# ClosedLoop_Drive_UserInterface.net
KiCad netlist of a schematic drawn in Altium Designer
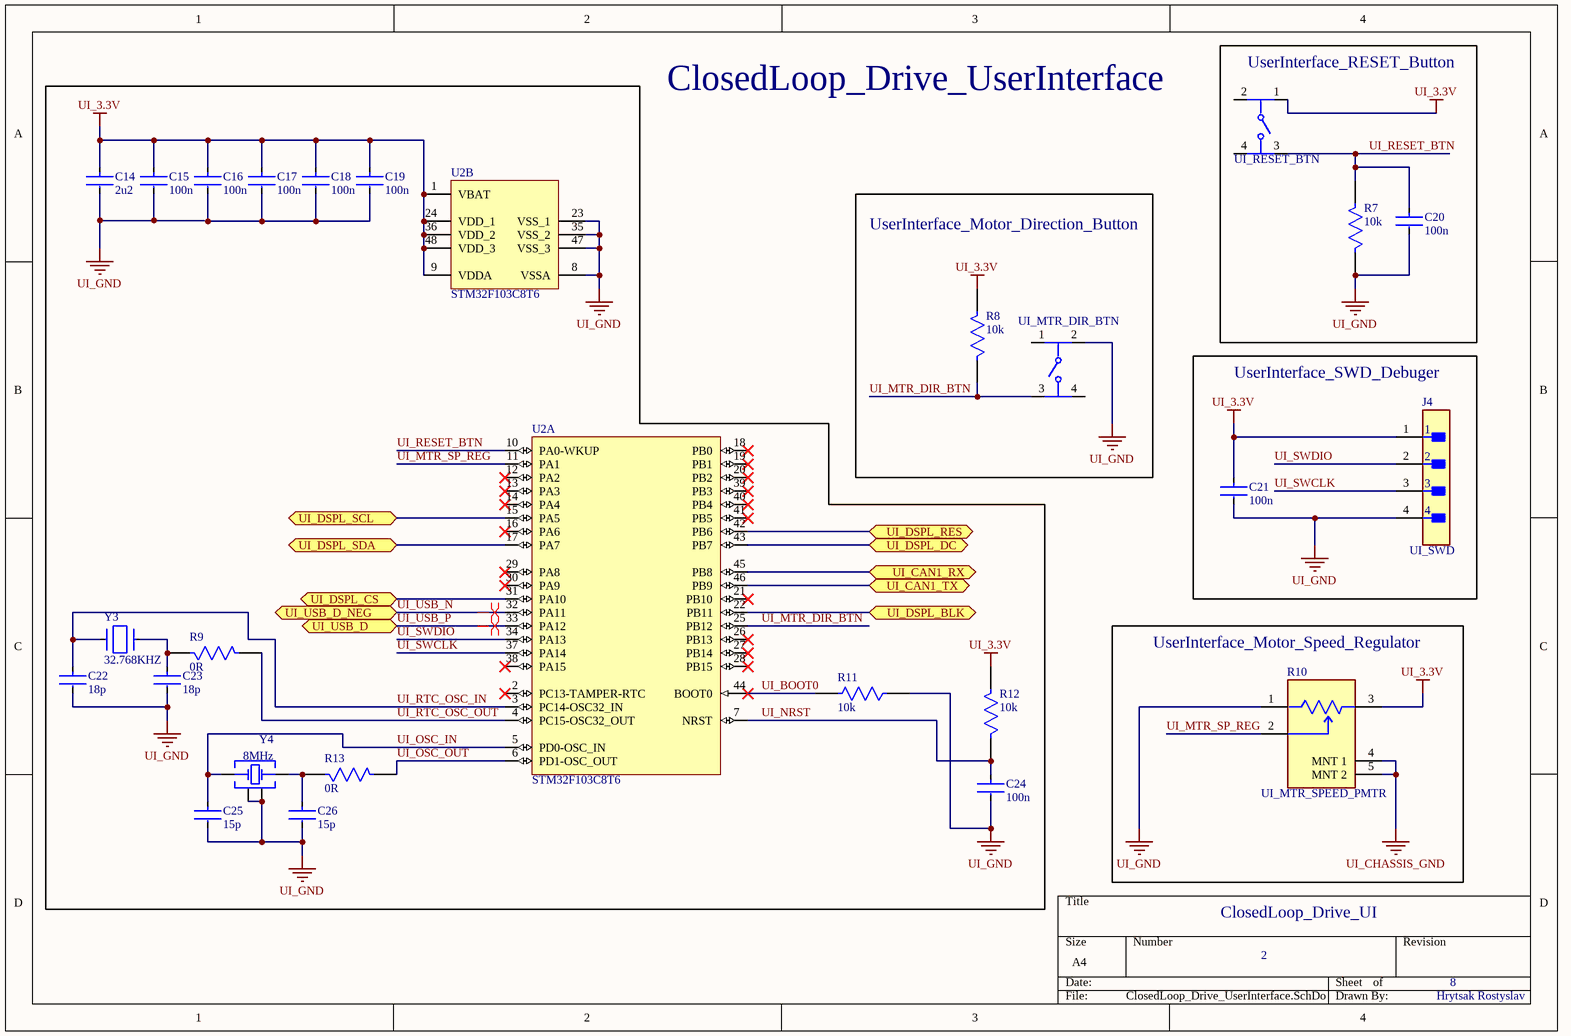
[diagram p0: ClosedLoop_Drive_UserInterface.SchDoc]

(export (version "E")
  (design (tool "Eeschema 10.0.6"))
  (components
    (comp (ref "C14")
      (value "2u2")
      (footprint "FP-0805-L_2_01_0_2-W_1_25-MFG")
      (description "0805")
      (fields (field (name "TOLERANCE") "10%"))
      (libsource (lib "Altium Content Vault") (part "b4654b650e69147ec39a6b967a45e02"))
    )
    (comp (ref "C15")
      (value "100n")
      (footprint "FP-0805-L_2_01_0_2-W_1_25-MFG")
      (description "0805")
      (fields (field (name "TOLERANCE") "10%"))
      (libsource (lib "Altium Content Vault") (part "b4654b650e69147ec39a6b967a45e02"))
    )
    (comp (ref "C16")
      (value "100n")
      (footprint "FP-0805-L_2_01_0_2-W_1_25-MFG")
      (description "0805")
      (fields (field (name "TOLERANCE") "10%"))
      (libsource (lib "Altium Content Vault") (part "b4654b650e69147ec39a6b967a45e02"))
    )
    (comp (ref "C17")
      (value "100n")
      (footprint "FP-0805-L_2_01_0_2-W_1_25-MFG")
      (description "0805")
      (fields (field (name "TOLERANCE") "10%"))
      (libsource (lib "Altium Content Vault") (part "b4654b650e69147ec39a6b967a45e02"))
    )
    (comp (ref "C18")
      (value "100n")
      (footprint "FP-0805-L_2_01_0_2-W_1_25-MFG")
      (description "0805")
      (fields (field (name "TOLERANCE") "10%"))
      (libsource (lib "Altium Content Vault") (part "b4654b650e69147ec39a6b967a45e02"))
    )
    (comp (ref "C19")
      (value "100n")
      (footprint "FP-0805-L_2_01_0_2-W_1_25-MFG")
      (description "0805")
      (fields (field (name "TOLERANCE") "10%"))
      (libsource (lib "Altium Content Vault") (part "b4654b650e69147ec39a6b967a45e02"))
    )
    (comp (ref "C20")
      (value "100n")
      (footprint "FP-0805-L_2_01_0_2-W_1_25-MFG")
      (description "0805")
      (fields (field (name "TOLERANCE") "10%"))
      (libsource (lib "Altium Content Vault") (part "b4654b650e69147ec39a6b967a45e02"))
    )
    (comp (ref "C21")
      (value "100n")
      (footprint "FP-0805-L_2_01_0_2-W_1_25-MFG")
      (description "0805")
      (fields (field (name "TOLERANCE") "10%"))
      (libsource (lib "Altium Content Vault") (part "b4654b650e69147ec39a6b967a45e02"))
    )
    (comp (ref "C22")
      (value "18p")
      (footprint "FP-0805-L_2_01_0_2-W_1_25-MFG")
      (description "0805")
      (fields (field (name "TOLERANCE") "10%"))
      (libsource (lib "Altium Content Vault") (part "b4654b650e69147ec39a6b967a45e02"))
    )
    (comp (ref "C23")
      (value "18p")
      (footprint "FP-0805-L_2_01_0_2-W_1_25-MFG")
      (description "0805")
      (fields (field (name "TOLERANCE") "10%"))
      (libsource (lib "Altium Content Vault") (part "b4654b650e69147ec39a6b967a45e02"))
    )
    (comp (ref "C24")
      (value "100n")
      (footprint "FP-0805-L_2_01_0_2-W_1_25-MFG")
      (description "0805")
      (fields (field (name "TOLERANCE") "10%"))
      (libsource (lib "Altium Content Vault") (part "b4654b650e69147ec39a6b967a45e02"))
    )
    (comp (ref "C25")
      (value "15p")
      (footprint "FP-0805-L_2_01_0_2-W_1_25-MFG")
      (description "0805")
      (fields (field (name "TOLERANCE") "10%"))
      (libsource (lib "Altium Content Vault") (part "b4654b650e69147ec39a6b967a45e02"))
    )
    (comp (ref "C26")
      (value "15p")
      (footprint "FP-0805-L_2_01_0_2-W_1_25-MFG")
      (description "0805")
      (fields (field (name "TOLERANCE") "10%"))
      (libsource (lib "Altium Content Vault") (part "b4654b650e69147ec39a6b967a45e02"))
    )
    (comp (ref "J4")
      (value "UI_SWD")
      (footprint "FP-TSW-104-22-G-S-MFG")
      (description "CONN HEADER VERT 4POS 2.54MM")
      (libsource (lib "Altium Content Vault") (part "299a8cea1bdcbc3624fe62c390fa72c"))
    )
    (comp (ref "R7")
      (value "10k")
      (footprint "FP-MCU0805-IPC_A")
      (description "0805")
      (fields (field (name "TOLERANCE") "0.5%"))
      (libsource (lib "Altium Content Vault") (part "1029c3af85768c4190bb7ad29bc67b5"))
    )
    (comp (ref "R8")
      (value "10k")
      (footprint "FP-MCU0805-IPC_A")
      (description "0805")
      (fields (field (name "TOLERANCE") "0.5%"))
      (libsource (lib "Altium Content Vault") (part "1029c3af85768c4190bb7ad29bc67b5"))
    )
    (comp (ref "R9")
      (value "0R")
      (footprint "FP-MCU0805-IPC_A")
      (description "0805")
      (fields (field (name "TOLERANCE") "0.5%"))
      (libsource (lib "Altium Content Vault") (part "1029c3af85768c4190bb7ad29bc67b5"))
    )
    (comp (ref "R10")
      (value "UI_MTR_SPEED_PMTR")
      (footprint "FP-PTV09A-4-MFG")
      (description "POT 10K OHM 1/20W CARBON LINEAR")
      (fields (field (name "TOLERANCE") "20%"))
      (libsource (lib "Altium Content Vault") (part "705d11b747745a787204d796a5f3d12"))
    )
    (comp (ref "R11")
      (value "10k")
      (footprint "FP-MCU0805-IPC_A")
      (description "0805")
      (fields (field (name "TOLERANCE") "0.5%"))
      (libsource (lib "Altium Content Vault") (part "1029c3af85768c4190bb7ad29bc67b5"))
    )
    (comp (ref "R12")
      (value "10k")
      (footprint "FP-MCU0805-IPC_A")
      (description "0805")
      (fields (field (name "TOLERANCE") "0.5%"))
      (libsource (lib "Altium Content Vault") (part "1029c3af85768c4190bb7ad29bc67b5"))
    )
    (comp (ref "R13")
      (value "0R")
      (footprint "FP-MCU0805-IPC_A")
      (description "0805")
      (fields (field (name "TOLERANCE") "0.5%"))
      (libsource (lib "Altium Content Vault") (part "1029c3af85768c4190bb7ad29bc67b5"))
    )
    (comp (ref "U2")
      (value "STM32F103C8T6")
      (footprint "STM-LQFP48_L")
      (libsource (lib "Altium Content Vault") (part "MC-ARM-STM32F103X8_B-SQ48"))
    )
    (comp (ref "UI_MTR_DIR_BTN")
      (value "~")
      (footprint "FP-1-1977223-9-MFG")
      (description "SWITCH TACTILE SPST-NO 0.05A 24V")
      (libsource (lib "Altium Content Vault") (part "b8895f3f4cefb76e1819d2863dba89b"))
    )
    (comp (ref "UI_RESET_BTN")
      (value "~")
      (footprint "FP-1-1977223-9-MFG")
      (description "SWITCH TACTILE SPST-NO 0.05A 24V")
      (libsource (lib "Altium Content Vault") (part "b8895f3f4cefb76e1819d2863dba89b"))
    )
    (comp (ref "Y3")
      (value "32.768KHZ")
      (footprint "FP-NX2012SA-MFG")
      (description "CRYSTAL 32.7680KHZ 12.5PF SMD")
      (libsource (lib "Altium Content Vault") (part "c23a69dc6c9e2f18f2079038eb95dd1"))
    )
    (comp (ref "Y4")
      (value "8MHz")
      (footprint "WE-XTAL_12SMX")
      (description "WE-XTAL Quartz Crystal")
      (libsource (lib "Altium Content Vault") (part "WE-XTAL_12SMX"))
    )
  )
  (nets
    (net (code "1") (name "/UI_BOOT0") (class "Default")
      (node (ref "R11") (pin "2") (pinfunction "2_2") (pintype "passive"))
      (node (ref "U2") (pin "44") (pinfunction "BOOT0_44") (pintype "input"))
    )
    (net (code "2") (name "/UI_CAN1_RX") (class "Default")
      (node (ref "U2") (pin "45") (pinfunction "PB8_45") (pintype "bidirectional"))
    )
    (net (code "3") (name "/UI_CAN1_TX") (class "Default")
      (node (ref "U2") (pin "46") (pinfunction "PB9_46") (pintype "bidirectional"))
    )
    (net (code "4") (name "/UI_DSPL_BLK") (class "Default")
      (node (ref "U2") (pin "22") (pinfunction "PB11_22") (pintype "bidirectional"))
    )
    (net (code "5") (name "/UI_DSPL_CS") (class "Default")
      (node (ref "U2") (pin "31") (pinfunction "PA10_31") (pintype "bidirectional"))
    )
    (net (code "6") (name "/UI_DSPL_DC") (class "Default")
      (node (ref "U2") (pin "43") (pinfunction "PB7_43") (pintype "bidirectional"))
    )
    (net (code "7") (name "/UI_DSPL_RES") (class "Default")
      (node (ref "U2") (pin "42") (pinfunction "PB6_42") (pintype "bidirectional"))
    )
    (net (code "8") (name "/UI_DSPL_SCL") (class "Default")
      (node (ref "U2") (pin "15") (pinfunction "PA5_15") (pintype "bidirectional"))
    )
    (net (code "9") (name "/UI_DSPL_SDA") (class "Default")
      (node (ref "U2") (pin "17") (pinfunction "PA7_17") (pintype "bidirectional"))
    )
    (net (code "10") (name "/UI_MTR_DIR_BTN") (class "Default")
      (node (ref "R8") (pin "1") (pinfunction "1_1") (pintype "passive"))
      (node (ref "U2") (pin "25") (pinfunction "PB12_25") (pintype "bidirectional"))
      (node (ref "UI_MTR_DIR_BTN") (pin "3") (pinfunction "3_3") (pintype "passive"))
    )
    (net (code "11") (name "/UI_MTR_SP_REG") (class "Default")
      (node (ref "R10") (pin "2") (pinfunction "2_2") (pintype "passive"))
      (node (ref "U2") (pin "11") (pinfunction "PA1_11") (pintype "bidirectional"))
    )
    (net (code "12") (name "/UI_NRST") (class "Default")
      (node (ref "C24") (pin "1") (pinfunction "1_1") (pintype "passive"))
      (node (ref "R12") (pin "1") (pinfunction "1_1") (pintype "passive"))
      (node (ref "U2") (pin "7") (pinfunction "NRST_7") (pintype "bidirectional"))
    )
    (net (code "13") (name "/UI_OSC_IN") (class "Default")
      (node (ref "C25") (pin "1") (pinfunction "1_1") (pintype "passive"))
      (node (ref "U2") (pin "5") (pinfunction "PD0-OSC_IN_5") (pintype "bidirectional"))
      (node (ref "Y4") (pin "3") (pinfunction "Crystal_3") (pintype "passive"))
    )
    (net (code "14") (name "/UI_OSC_OUT") (class "Default")
      (node (ref "R13") (pin "2") (pinfunction "2_2") (pintype "passive"))
      (node (ref "U2") (pin "6") (pinfunction "PD1-OSC_OUT_6") (pintype "bidirectional"))
    )
    (net (code "15") (name "/UI_RESET_BTN") (class "Default")
      (node (ref "C20") (pin "1") (pinfunction "1_1") (pintype "passive"))
      (node (ref "R7") (pin "2") (pinfunction "2_2") (pintype "passive"))
      (node (ref "U2") (pin "10") (pinfunction "PA0-WKUP_10") (pintype "bidirectional"))
      (node (ref "UI_RESET_BTN") (pin "3") (pinfunction "3_3") (pintype "passive"))
    )
    (net (code "16") (name "/UI_RTC_OSC_IN") (class "Default")
      (node (ref "C22") (pin "1") (pinfunction "1_1") (pintype "passive"))
      (node (ref "U2") (pin "3") (pinfunction "PC14-OSC32_IN_3") (pintype "bidirectional"))
      (node (ref "Y3") (pin "2") (pinfunction "2_2") (pintype "passive"))
    )
    (net (code "17") (name "/UI_RTC_OSC_OUT") (class "Default")
      (node (ref "R9") (pin "2") (pinfunction "2_2") (pintype "passive"))
      (node (ref "U2") (pin "4") (pinfunction "PC15-OSC32_OUT_4") (pintype "bidirectional"))
    )
    (net (code "18") (name "/UI_SWCLK") (class "Default")
      (node (ref "J4") (pin "3") (pinfunction "3_3") (pintype "passive"))
      (node (ref "U2") (pin "37") (pinfunction "PA14_37") (pintype "bidirectional"))
    )
    (net (code "19") (name "/UI_SWDIO") (class "Default")
      (node (ref "J4") (pin "2") (pinfunction "2_2") (pintype "passive"))
      (node (ref "U2") (pin "34") (pinfunction "PA13_34") (pintype "bidirectional"))
    )
    (net (code "20") (name "/UI_USB_N") (class "Default")
      (node (ref "U2") (pin "32") (pinfunction "PA11_32") (pintype "bidirectional"))
    )
    (net (code "21") (name "/UI_USB_P") (class "Default")
      (node (ref "U2") (pin "33") (pinfunction "PA12_33") (pintype "bidirectional"))
    )
    (net (code "22") (name "Net-(C23-Pad1)") (class "Default")
      (node (ref "C23") (pin "1") (pinfunction "1_1") (pintype "passive"))
      (node (ref "R9") (pin "1") (pinfunction "1_1") (pintype "passive"))
      (node (ref "Y3") (pin "1") (pinfunction "1_1") (pintype "passive"))
    )
    (net (code "23") (name "Net-(C26-Pad1)") (class "Default")
      (node (ref "C26") (pin "1") (pinfunction "1_1") (pintype "passive"))
      (node (ref "R13") (pin "1") (pinfunction "1_1") (pintype "passive"))
      (node (ref "Y4") (pin "1") (pinfunction "Crystal_1") (pintype "passive"))
    )
    (net (code "24") (name "UI_3.3V") (class "Default")
      (node (ref "C14") (pin "1") (pinfunction "1_1") (pintype "passive"))
      (node (ref "C15") (pin "1") (pinfunction "1_1") (pintype "passive"))
      (node (ref "C16") (pin "1") (pinfunction "1_1") (pintype "passive"))
      (node (ref "C17") (pin "1") (pinfunction "1_1") (pintype "passive"))
      (node (ref "C18") (pin "1") (pinfunction "1_1") (pintype "passive"))
      (node (ref "C19") (pin "1") (pinfunction "1_1") (pintype "passive"))
      (node (ref "C21") (pin "1") (pinfunction "1_1") (pintype "passive"))
      (node (ref "J4") (pin "1") (pinfunction "1_1") (pintype "passive"))
      (node (ref "R10") (pin "3") (pinfunction "3_3") (pintype "passive"))
      (node (ref "R12") (pin "2") (pinfunction "2_2") (pintype "passive"))
      (node (ref "R8") (pin "2") (pinfunction "2_2") (pintype "passive"))
      (node (ref "U2") (pin "1") (pinfunction "VBAT_1") (pintype "power_in"))
      (node (ref "U2") (pin "24") (pinfunction "VDD_1_24") (pintype "power_in"))
      (node (ref "U2") (pin "36") (pinfunction "VDD_2_36") (pintype "power_in"))
      (node (ref "U2") (pin "48") (pinfunction "VDD_3_48") (pintype "power_in"))
      (node (ref "U2") (pin "9") (pinfunction "VDDA_9") (pintype "power_in"))
      (node (ref "UI_RESET_BTN") (pin "1") (pinfunction "1_1") (pintype "passive"))
    )
    (net (code "25") (name "UI_CHASSIS_GND") (class "Default")
      (node (ref "R10") (pin "4") (pinfunction "MNT_1_4") (pintype "passive"))
      (node (ref "R10") (pin "5") (pinfunction "MNT_2_5") (pintype "passive"))
    )
    (net (code "26") (name "UI_GND") (class "Default")
      (node (ref "C14") (pin "2") (pinfunction "2_2") (pintype "passive"))
      (node (ref "C15") (pin "2") (pinfunction "2_2") (pintype "passive"))
      (node (ref "C16") (pin "2") (pinfunction "2_2") (pintype "passive"))
      (node (ref "C17") (pin "2") (pinfunction "2_2") (pintype "passive"))
      (node (ref "C18") (pin "2") (pinfunction "2_2") (pintype "passive"))
      (node (ref "C19") (pin "2") (pinfunction "2_2") (pintype "passive"))
      (node (ref "C20") (pin "2") (pinfunction "2_2") (pintype "passive"))
      (node (ref "C21") (pin "2") (pinfunction "2_2") (pintype "passive"))
      (node (ref "C22") (pin "2") (pinfunction "2_2") (pintype "passive"))
      (node (ref "C23") (pin "2") (pinfunction "2_2") (pintype "passive"))
      (node (ref "C24") (pin "2") (pinfunction "2_2") (pintype "passive"))
      (node (ref "C25") (pin "2") (pinfunction "2_2") (pintype "passive"))
      (node (ref "C26") (pin "2") (pinfunction "2_2") (pintype "passive"))
      (node (ref "J4") (pin "4") (pinfunction "4_4") (pintype "passive"))
      (node (ref "R10") (pin "1") (pinfunction "1_1") (pintype "passive"))
      (node (ref "R11") (pin "1") (pinfunction "1_1") (pintype "passive"))
      (node (ref "R7") (pin "1") (pinfunction "1_1") (pintype "passive"))
      (node (ref "U2") (pin "23") (pinfunction "VSS_1_23") (pintype "power_in"))
      (node (ref "U2") (pin "35") (pinfunction "VSS_2_35") (pintype "power_in"))
      (node (ref "U2") (pin "47") (pinfunction "VSS_3_47") (pintype "power_in"))
      (node (ref "U2") (pin "8") (pinfunction "VSSA_8") (pintype "power_in"))
      (node (ref "UI_MTR_DIR_BTN") (pin "2") (pinfunction "2_2") (pintype "passive"))
      (node (ref "Y4") (pin "2") (pinfunction "GND_2") (pintype "passive"))
      (node (ref "Y4") (pin "4") (pinfunction "GND_4") (pintype "passive"))
    )
    (net (code "27") (name "unconnected-(U2A-PA2-Pad12)") (class "Default")
      (node (ref "U2") (pin "12") (pinfunction "PA2_12") (pintype "bidirectional+no_connect"))
    )
    (net (code "28") (name "unconnected-(U2A-PA3-Pad13)") (class "Default")
      (node (ref "U2") (pin "13") (pinfunction "PA3_13") (pintype "bidirectional+no_connect"))
    )
    (net (code "29") (name "unconnected-(U2A-PA4-Pad14)") (class "Default")
      (node (ref "U2") (pin "14") (pinfunction "PA4_14") (pintype "bidirectional+no_connect"))
    )
    (net (code "30") (name "unconnected-(U2A-PA6-Pad16)") (class "Default")
      (node (ref "U2") (pin "16") (pinfunction "PA6_16") (pintype "bidirectional+no_connect"))
    )
    (net (code "31") (name "unconnected-(U2A-PA8-Pad29)") (class "Default")
      (node (ref "U2") (pin "29") (pinfunction "PA8_29") (pintype "bidirectional+no_connect"))
    )
    (net (code "32") (name "unconnected-(U2A-PA9-Pad30)") (class "Default")
      (node (ref "U2") (pin "30") (pinfunction "PA9_30") (pintype "bidirectional+no_connect"))
    )
    (net (code "33") (name "unconnected-(U2A-PA15-Pad38)") (class "Default")
      (node (ref "U2") (pin "38") (pinfunction "PA15_38") (pintype "bidirectional+no_connect"))
    )
    (net (code "34") (name "unconnected-(U2A-PB0-Pad18)") (class "Default")
      (node (ref "U2") (pin "18") (pinfunction "PB0_18") (pintype "bidirectional+no_connect"))
    )
    (net (code "35") (name "unconnected-(U2A-PB1-Pad19)") (class "Default")
      (node (ref "U2") (pin "19") (pinfunction "PB1_19") (pintype "bidirectional+no_connect"))
    )
    (net (code "36") (name "unconnected-(U2A-PB2-Pad20)") (class "Default")
      (node (ref "U2") (pin "20") (pinfunction "PB2_20") (pintype "bidirectional+no_connect"))
    )
    (net (code "37") (name "unconnected-(U2A-PB3-Pad39)") (class "Default")
      (node (ref "U2") (pin "39") (pinfunction "PB3_39") (pintype "bidirectional+no_connect"))
    )
    (net (code "38") (name "unconnected-(U2A-PB4-Pad40)") (class "Default")
      (node (ref "U2") (pin "40") (pinfunction "PB4_40") (pintype "bidirectional+no_connect"))
    )
    (net (code "39") (name "unconnected-(U2A-PB5-Pad41)") (class "Default")
      (node (ref "U2") (pin "41") (pinfunction "PB5_41") (pintype "bidirectional+no_connect"))
    )
    (net (code "40") (name "unconnected-(U2A-PB10-Pad21)") (class "Default")
      (node (ref "U2") (pin "21") (pinfunction "PB10_21") (pintype "bidirectional+no_connect"))
    )
    (net (code "41") (name "unconnected-(U2A-PB13-Pad26)") (class "Default")
      (node (ref "U2") (pin "26") (pinfunction "PB13_26") (pintype "bidirectional+no_connect"))
    )
    (net (code "42") (name "unconnected-(U2A-PB14-Pad27)") (class "Default")
      (node (ref "U2") (pin "27") (pinfunction "PB14_27") (pintype "bidirectional+no_connect"))
    )
    (net (code "43") (name "unconnected-(U2A-PB15-Pad28)") (class "Default")
      (node (ref "U2") (pin "28") (pinfunction "PB15_28") (pintype "bidirectional+no_connect"))
    )
    (net (code "44") (name "unconnected-(U2A-PC13-TAMPER-RTC-Pad2)") (class "Default")
      (node (ref "U2") (pin "2") (pinfunction "PC13-TAMPER-RTC_2") (pintype "bidirectional+no_connect"))
    )
    (net (code "45") (name "unconnected-(UI_MTR_DIR_BTN-Pad1)") (class "Default")
      (node (ref "UI_MTR_DIR_BTN") (pin "1") (pinfunction "1_1") (pintype "passive"))
    )
    (net (code "46") (name "unconnected-(UI_MTR_DIR_BTN-Pad4)") (class "Default")
      (node (ref "UI_MTR_DIR_BTN") (pin "4") (pinfunction "4_4") (pintype "passive"))
    )
    (net (code "47") (name "unconnected-(UI_RESET_BTN-Pad2)") (class "Default")
      (node (ref "UI_RESET_BTN") (pin "2") (pinfunction "2_2") (pintype "passive"))
    )
    (net (code "48") (name "unconnected-(UI_RESET_BTN-Pad4)") (class "Default")
      (node (ref "UI_RESET_BTN") (pin "4") (pinfunction "4_4") (pintype "passive"))
    )
  )
)
